# SCH_Meouth_Display_2025-10-24.net
KiCad netlist of a schematic drawn in EasyEDA
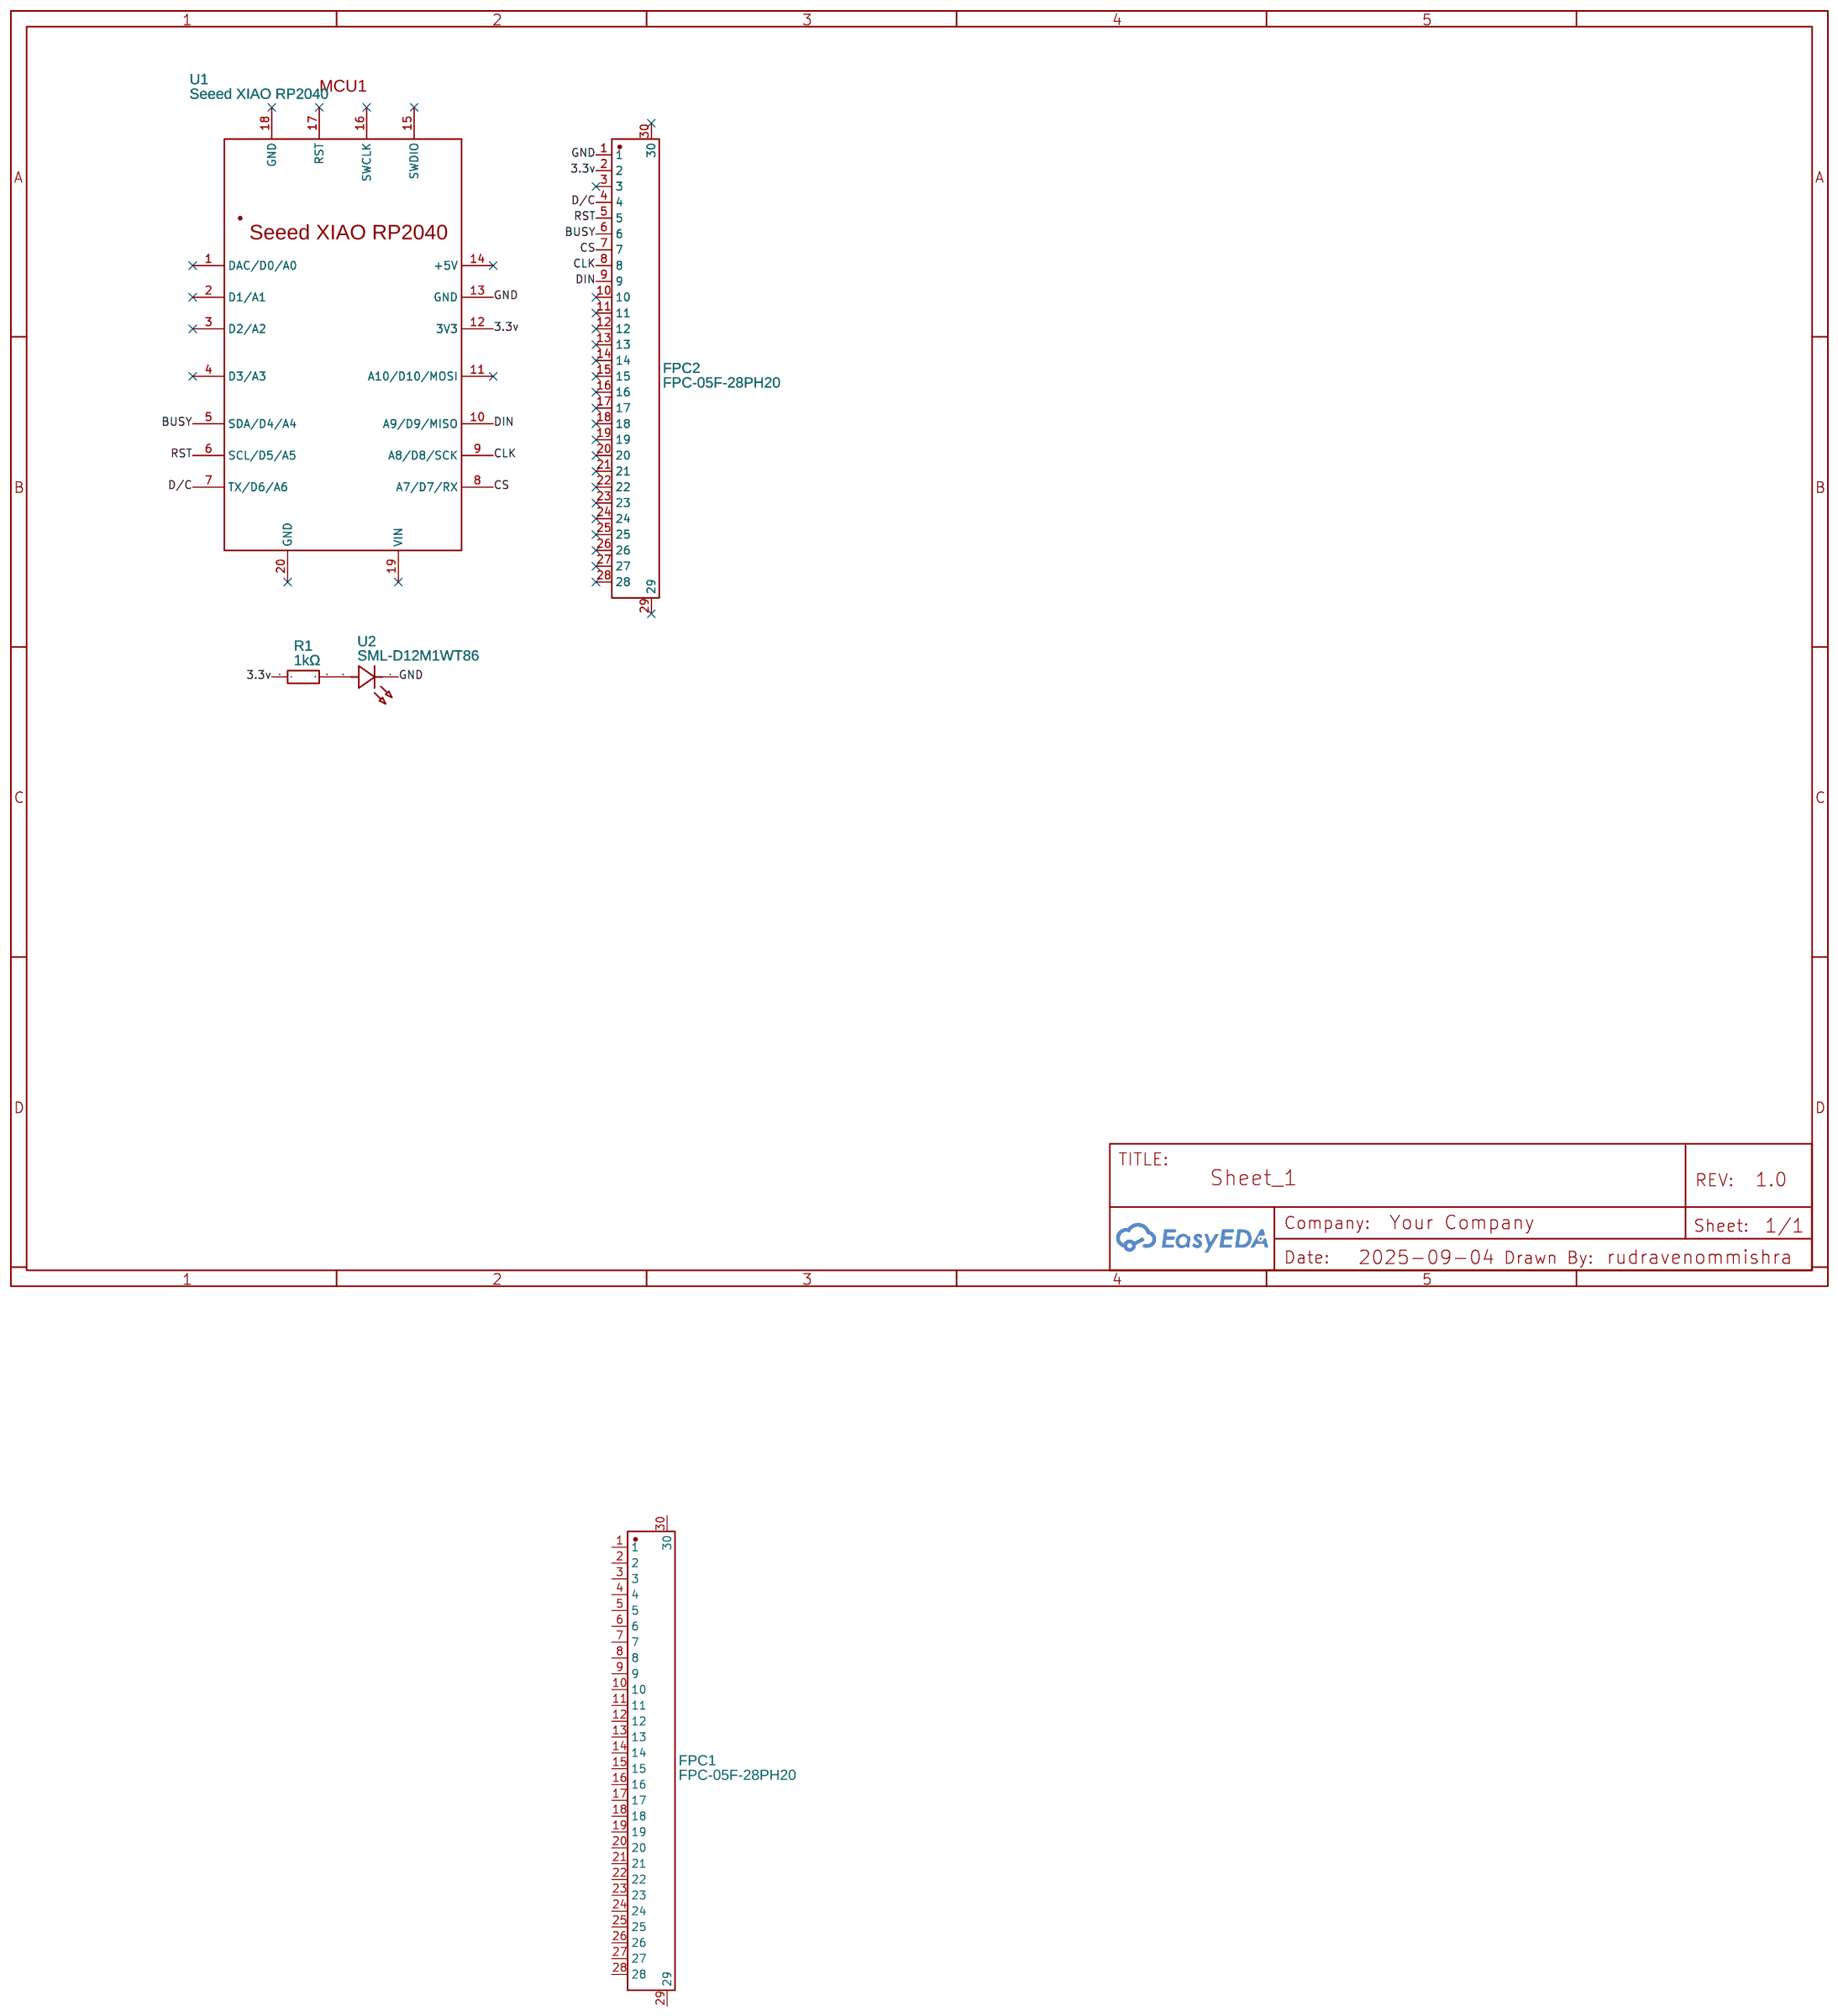
[diagram p0: schematic sheet]

(export (version "E")
  (design (tool "Eeschema 10.0.6"))
  (components
    (comp (ref "FPC1")
      (value "FPC-05F-28PH20")
      (fields (field (name "Manufacturer") "XUNPU(讯普)"))
      (libsource (lib "") (part "FPC-05F-28PH20"))
    )
    (comp (ref "FPC2")
      (value "FPC-05F-28PH20")
      (fields (field (name "Manufacturer") "XUNPU(讯普)"))
      (libsource (lib "") (part "FPC-05F-28PH20"))
    )
    (comp (ref "R1")
      (value "1kΩ")
      (fields
        (field (name "Manufacturer Part") "0603WAF1001T5E")
        (field (name "Manufacturer") "UNI-ROYAL(厚声)")
      )
      (libsource (lib "") (part "0603WAF1001T5E"))
    )
    (comp (ref "U1")
      (value "Seeed XIAO RP2040")
      (fields (field (name "Manufacturer Part") "Seeed XIAO RP2040("))
      (libsource (lib "") (part "Seeed XIAO RP2040"))
    )
    (comp (ref "U2")
      (value "SML-D12M1WT86")
      (fields (field (name "Manufacturer") "ROHM(罗姆)"))
      (libsource (lib "") (part "SML-D12M1WT86"))
    )
  )
  (nets
    (net (code "1") (name "/3.3v") (class "Default")
      (node (ref "FPC2") (pin "2") (pinfunction "2_2") (pintype "unspecified"))
      (node (ref "R1") (pin "1") (pinfunction "1_1") (pintype "input"))
      (node (ref "U1") (pin "12") (pinfunction "3V3_12") (pintype "unspecified"))
    )
    (net (code "2") (name "/BUSY") (class "Default")
      (node (ref "FPC2") (pin "6") (pinfunction "6_6") (pintype "unspecified"))
      (node (ref "U1") (pin "5") (pinfunction "SDA/D4/A4_5") (pintype "unspecified"))
    )
    (net (code "3") (name "/CLK") (class "Default")
      (node (ref "FPC2") (pin "8") (pinfunction "8_8") (pintype "unspecified"))
      (node (ref "U1") (pin "9") (pinfunction "A8/D8/SCK_9") (pintype "unspecified"))
    )
    (net (code "4") (name "/CS") (class "Default")
      (node (ref "FPC2") (pin "7") (pinfunction "7_7") (pintype "unspecified"))
      (node (ref "U1") (pin "8") (pinfunction "A7/D7/RX_8") (pintype "unspecified"))
    )
    (net (code "5") (name "/DIN") (class "Default")
      (node (ref "FPC2") (pin "9") (pinfunction "9_9") (pintype "unspecified"))
      (node (ref "U1") (pin "10") (pinfunction "A9/D9/MISO_10") (pintype "unspecified"))
    )
    (net (code "6") (name "/D{slash}C") (class "Default")
      (node (ref "FPC2") (pin "4") (pinfunction "4_4") (pintype "unspecified"))
      (node (ref "U1") (pin "7") (pinfunction "TX/D6/A6_7") (pintype "unspecified"))
    )
    (net (code "7") (name "/GND") (class "Default")
      (node (ref "FPC2") (pin "1") (pinfunction "1_1") (pintype "unspecified"))
      (node (ref "U1") (pin "13") (pinfunction "GND_13") (pintype "unspecified"))
      (node (ref "U2") (pin "1") (pinfunction "K_1") (pintype "unspecified"))
    )
    (net (code "8") (name "/RST") (class "Default")
      (node (ref "FPC2") (pin "5") (pinfunction "5_5") (pintype "unspecified"))
      (node (ref "U1") (pin "6") (pinfunction "SCL/D5/A5_6") (pintype "unspecified"))
    )
    (net (code "9") (name "Net-(U2-A)") (class "Default")
      (node (ref "R1") (pin "2") (pinfunction "2_2") (pintype "input"))
      (node (ref "U2") (pin "2") (pinfunction "A_2") (pintype "unspecified"))
    )
    (net (code "10") (name "unconnected-(FPC1-Pad1)") (class "Default")
      (node (ref "FPC1") (pin "1") (pinfunction "1_1") (pintype "unspecified"))
    )
    (net (code "11") (name "unconnected-(FPC1-Pad2)") (class "Default")
      (node (ref "FPC1") (pin "2") (pinfunction "2_2") (pintype "unspecified"))
    )
    (net (code "12") (name "unconnected-(FPC1-Pad3)") (class "Default")
      (node (ref "FPC1") (pin "3") (pinfunction "3_3") (pintype "unspecified"))
    )
    (net (code "13") (name "unconnected-(FPC1-Pad4)") (class "Default")
      (node (ref "FPC1") (pin "4") (pinfunction "4_4") (pintype "unspecified"))
    )
    (net (code "14") (name "unconnected-(FPC1-Pad5)") (class "Default")
      (node (ref "FPC1") (pin "5") (pinfunction "5_5") (pintype "unspecified"))
    )
    (net (code "15") (name "unconnected-(FPC1-Pad6)") (class "Default")
      (node (ref "FPC1") (pin "6") (pinfunction "6_6") (pintype "unspecified"))
    )
    (net (code "16") (name "unconnected-(FPC1-Pad7)") (class "Default")
      (node (ref "FPC1") (pin "7") (pinfunction "7_7") (pintype "unspecified"))
    )
    (net (code "17") (name "unconnected-(FPC1-Pad8)") (class "Default")
      (node (ref "FPC1") (pin "8") (pinfunction "8_8") (pintype "unspecified"))
    )
    (net (code "18") (name "unconnected-(FPC1-Pad9)") (class "Default")
      (node (ref "FPC1") (pin "9") (pinfunction "9_9") (pintype "unspecified"))
    )
    (net (code "19") (name "unconnected-(FPC1-Pad10)") (class "Default")
      (node (ref "FPC1") (pin "10") (pinfunction "10_10") (pintype "unspecified"))
    )
    (net (code "20") (name "unconnected-(FPC1-Pad11)") (class "Default")
      (node (ref "FPC1") (pin "11") (pinfunction "11_11") (pintype "unspecified"))
    )
    (net (code "21") (name "unconnected-(FPC1-Pad12)") (class "Default")
      (node (ref "FPC1") (pin "12") (pinfunction "12_12") (pintype "unspecified"))
    )
    (net (code "22") (name "unconnected-(FPC1-Pad13)") (class "Default")
      (node (ref "FPC1") (pin "13") (pinfunction "13_13") (pintype "unspecified"))
    )
    (net (code "23") (name "unconnected-(FPC1-Pad14)") (class "Default")
      (node (ref "FPC1") (pin "14") (pinfunction "14_14") (pintype "unspecified"))
    )
    (net (code "24") (name "unconnected-(FPC1-Pad15)") (class "Default")
      (node (ref "FPC1") (pin "15") (pinfunction "15_15") (pintype "unspecified"))
    )
    (net (code "25") (name "unconnected-(FPC1-Pad16)") (class "Default")
      (node (ref "FPC1") (pin "16") (pinfunction "16_16") (pintype "unspecified"))
    )
    (net (code "26") (name "unconnected-(FPC1-Pad17)") (class "Default")
      (node (ref "FPC1") (pin "17") (pinfunction "17_17") (pintype "unspecified"))
    )
    (net (code "27") (name "unconnected-(FPC1-Pad18)") (class "Default")
      (node (ref "FPC1") (pin "18") (pinfunction "18_18") (pintype "unspecified"))
    )
    (net (code "28") (name "unconnected-(FPC1-Pad19)") (class "Default")
      (node (ref "FPC1") (pin "19") (pinfunction "19_19") (pintype "unspecified"))
    )
    (net (code "29") (name "unconnected-(FPC1-Pad20)") (class "Default")
      (node (ref "FPC1") (pin "20") (pinfunction "20_20") (pintype "unspecified"))
    )
    (net (code "30") (name "unconnected-(FPC1-Pad21)") (class "Default")
      (node (ref "FPC1") (pin "21") (pinfunction "21_21") (pintype "unspecified"))
    )
    (net (code "31") (name "unconnected-(FPC1-Pad22)") (class "Default")
      (node (ref "FPC1") (pin "22") (pinfunction "22_22") (pintype "unspecified"))
    )
    (net (code "32") (name "unconnected-(FPC1-Pad23)") (class "Default")
      (node (ref "FPC1") (pin "23") (pinfunction "23_23") (pintype "unspecified"))
    )
    (net (code "33") (name "unconnected-(FPC1-Pad24)") (class "Default")
      (node (ref "FPC1") (pin "24") (pinfunction "24_24") (pintype "unspecified"))
    )
    (net (code "34") (name "unconnected-(FPC1-Pad25)") (class "Default")
      (node (ref "FPC1") (pin "25") (pinfunction "25_25") (pintype "unspecified"))
    )
    (net (code "35") (name "unconnected-(FPC1-Pad26)") (class "Default")
      (node (ref "FPC1") (pin "26") (pinfunction "26_26") (pintype "unspecified"))
    )
    (net (code "36") (name "unconnected-(FPC1-Pad27)") (class "Default")
      (node (ref "FPC1") (pin "27") (pinfunction "27_27") (pintype "unspecified"))
    )
    (net (code "37") (name "unconnected-(FPC1-Pad28)") (class "Default")
      (node (ref "FPC1") (pin "28") (pinfunction "28_28") (pintype "unspecified"))
    )
    (net (code "38") (name "unconnected-(FPC1-Pad29)") (class "Default")
      (node (ref "FPC1") (pin "29") (pinfunction "29_29") (pintype "unspecified"))
    )
    (net (code "39") (name "unconnected-(FPC1-Pad30)") (class "Default")
      (node (ref "FPC1") (pin "30") (pinfunction "30_30") (pintype "unspecified"))
    )
    (net (code "40") (name "unconnected-(FPC2-Pad3)") (class "Default")
      (node (ref "FPC2") (pin "3") (pinfunction "3_3") (pintype "unspecified+no_connect"))
    )
    (net (code "41") (name "unconnected-(FPC2-Pad10)") (class "Default")
      (node (ref "FPC2") (pin "10") (pinfunction "10_10") (pintype "unspecified+no_connect"))
    )
    (net (code "42") (name "unconnected-(FPC2-Pad11)") (class "Default")
      (node (ref "FPC2") (pin "11") (pinfunction "11_11") (pintype "unspecified+no_connect"))
    )
    (net (code "43") (name "unconnected-(FPC2-Pad12)") (class "Default")
      (node (ref "FPC2") (pin "12") (pinfunction "12_12") (pintype "unspecified+no_connect"))
    )
    (net (code "44") (name "unconnected-(FPC2-Pad13)") (class "Default")
      (node (ref "FPC2") (pin "13") (pinfunction "13_13") (pintype "unspecified+no_connect"))
    )
    (net (code "45") (name "unconnected-(FPC2-Pad14)") (class "Default")
      (node (ref "FPC2") (pin "14") (pinfunction "14_14") (pintype "unspecified+no_connect"))
    )
    (net (code "46") (name "unconnected-(FPC2-Pad15)") (class "Default")
      (node (ref "FPC2") (pin "15") (pinfunction "15_15") (pintype "unspecified+no_connect"))
    )
    (net (code "47") (name "unconnected-(FPC2-Pad16)") (class "Default")
      (node (ref "FPC2") (pin "16") (pinfunction "16_16") (pintype "unspecified+no_connect"))
    )
    (net (code "48") (name "unconnected-(FPC2-Pad17)") (class "Default")
      (node (ref "FPC2") (pin "17") (pinfunction "17_17") (pintype "unspecified+no_connect"))
    )
    (net (code "49") (name "unconnected-(FPC2-Pad18)") (class "Default")
      (node (ref "FPC2") (pin "18") (pinfunction "18_18") (pintype "unspecified+no_connect"))
    )
    (net (code "50") (name "unconnected-(FPC2-Pad19)") (class "Default")
      (node (ref "FPC2") (pin "19") (pinfunction "19_19") (pintype "unspecified+no_connect"))
    )
    (net (code "51") (name "unconnected-(FPC2-Pad20)") (class "Default")
      (node (ref "FPC2") (pin "20") (pinfunction "20_20") (pintype "unspecified+no_connect"))
    )
    (net (code "52") (name "unconnected-(FPC2-Pad21)") (class "Default")
      (node (ref "FPC2") (pin "21") (pinfunction "21_21") (pintype "unspecified+no_connect"))
    )
    (net (code "53") (name "unconnected-(FPC2-Pad22)") (class "Default")
      (node (ref "FPC2") (pin "22") (pinfunction "22_22") (pintype "unspecified+no_connect"))
    )
    (net (code "54") (name "unconnected-(FPC2-Pad23)") (class "Default")
      (node (ref "FPC2") (pin "23") (pinfunction "23_23") (pintype "unspecified+no_connect"))
    )
    (net (code "55") (name "unconnected-(FPC2-Pad24)") (class "Default")
      (node (ref "FPC2") (pin "24") (pinfunction "24_24") (pintype "unspecified+no_connect"))
    )
    (net (code "56") (name "unconnected-(FPC2-Pad25)") (class "Default")
      (node (ref "FPC2") (pin "25") (pinfunction "25_25") (pintype "unspecified+no_connect"))
    )
    (net (code "57") (name "unconnected-(FPC2-Pad26)") (class "Default")
      (node (ref "FPC2") (pin "26") (pinfunction "26_26") (pintype "unspecified+no_connect"))
    )
    (net (code "58") (name "unconnected-(FPC2-Pad27)") (class "Default")
      (node (ref "FPC2") (pin "27") (pinfunction "27_27") (pintype "unspecified+no_connect"))
    )
    (net (code "59") (name "unconnected-(FPC2-Pad28)") (class "Default")
      (node (ref "FPC2") (pin "28") (pinfunction "28_28") (pintype "unspecified+no_connect"))
    )
    (net (code "60") (name "unconnected-(FPC2-Pad29)") (class "Default")
      (node (ref "FPC2") (pin "29") (pinfunction "29_29") (pintype "unspecified+no_connect"))
    )
    (net (code "61") (name "unconnected-(FPC2-Pad30)") (class "Default")
      (node (ref "FPC2") (pin "30") (pinfunction "30_30") (pintype "unspecified+no_connect"))
    )
    (net (code "62") (name "unconnected-(U1-+5V-Pad14)") (class "Default")
      (node (ref "U1") (pin "14") (pinfunction "+5V_14") (pintype "unspecified+no_connect"))
    )
    (net (code "63") (name "unconnected-(U1-A10{slash}D10{slash}MOSI-Pad11)") (class "Default")
      (node (ref "U1") (pin "11") (pinfunction "A10/D10/MOSI_11") (pintype "unspecified+no_connect"))
    )
    (net (code "64") (name "unconnected-(U1-D1{slash}A1-Pad2)") (class "Default")
      (node (ref "U1") (pin "2") (pinfunction "D1/A1_2") (pintype "unspecified+no_connect"))
    )
    (net (code "65") (name "unconnected-(U1-D2{slash}A2-Pad3)") (class "Default")
      (node (ref "U1") (pin "3") (pinfunction "D2/A2_3") (pintype "unspecified+no_connect"))
    )
    (net (code "66") (name "unconnected-(U1-D3{slash}A3-Pad4)") (class "Default")
      (node (ref "U1") (pin "4") (pinfunction "D3/A3_4") (pintype "unspecified+no_connect"))
    )
    (net (code "67") (name "unconnected-(U1-DAC{slash}D0{slash}A0-Pad1)") (class "Default")
      (node (ref "U1") (pin "1") (pinfunction "DAC/D0/A0_1") (pintype "unspecified+no_connect"))
    )
    (net (code "68") (name "unconnected-(U1-GND-Pad18)") (class "Default")
      (node (ref "U1") (pin "18") (pinfunction "GND_18") (pintype "unspecified+no_connect"))
    )
    (net (code "69") (name "unconnected-(U1-GND-Pad20)") (class "Default")
      (node (ref "U1") (pin "20") (pinfunction "GND_20") (pintype "unspecified+no_connect"))
    )
    (net (code "70") (name "unconnected-(U1-RST-Pad17)") (class "Default")
      (node (ref "U1") (pin "17") (pinfunction "RST_17") (pintype "unspecified+no_connect"))
    )
    (net (code "71") (name "unconnected-(U1-SWCLK-Pad16)") (class "Default")
      (node (ref "U1") (pin "16") (pinfunction "SWCLK_16") (pintype "unspecified+no_connect"))
    )
    (net (code "72") (name "unconnected-(U1-SWDIO-Pad15)") (class "Default")
      (node (ref "U1") (pin "15") (pinfunction "SWDIO_15") (pintype "unspecified+no_connect"))
    )
    (net (code "73") (name "unconnected-(U1-VIN-Pad19)") (class "Default")
      (node (ref "U1") (pin "19") (pinfunction "VIN_19") (pintype "unspecified+no_connect"))
    )
  )
)
